# 03_-IMU.net
KiCad netlist of a schematic drawn in Altium Designer
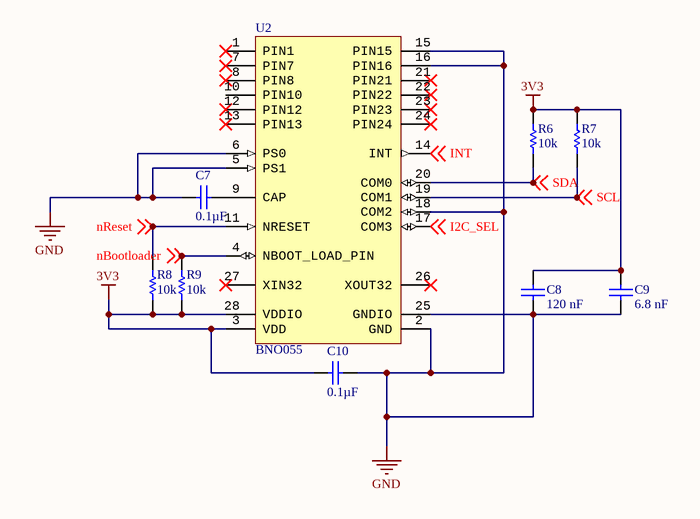
[diagram p0: [03]-IMU.SchDoc]

(export (version "E")
  (design (tool "Eeschema 10.0.6"))
  (components
    (comp (ref "C7")
      (value "C2012X7R2A104K125AA")
      (footprint "CAPC2013X145X20ML20")
      (description "Chip Capacitor, 100 nF, +/- 10%, 100 V, -55 to 1255 degC, 0805 (2012 Metric), RoHS, Tape and Reel")
      (fields
        (field (name "MANUFACTURER") "TDK")
        (field (name "TOLERANCE") "±10%")
        (field (name "CAPACITANCE") "0.1µF")
      )
      (libsource (lib "Altium Content Vault") (part "CAP-NP-2"))
    )
    (comp (ref "C8")
      (value "120 nF")
      (footprint "CAPC1005X55X25ML05T10")
      (description "120 nF Capacitor")
      (fields (field (name "PART NUMBER") "GRM155R71H123KA12D") (field (name "MANUFACTURER") "Murata"))
      (libsource (lib "Altium Content Vault") (part "CAP"))
    )
    (comp (ref "C9")
      (value "6.8 nF")
      (footprint "CAPC0603X33X15NL03T05")
      (fields (field (name "PART NUMBER") "GRM033R71A682KA01D") (field (name "MANUFACTURER") "Murata"))
      (libsource (lib "Altium Content Vault") (part "CAP"))
    )
    (comp (ref "C10")
      (value "C2012X7R2A104K125AA")
      (footprint "CAPC2013X145X20ML20")
      (description "Chip Capacitor, 100 nF, +/- 10%, 100 V, -55 to 1255 degC, 0805 (2012 Metric), RoHS, Tape and Reel")
      (fields
        (field (name "MANUFACTURER") "TDK")
        (field (name "TOLERANCE") "±10%")
        (field (name "CAPACITANCE") "0.1µF")
      )
      (libsource (lib "Altium Content Vault") (part "CAP-NP-2"))
    )
    (comp (ref "R6")
      (value "RC0805JR-0710KL")
      (footprint "RESC2013X60X35ML10T20")
      (description "Chip Resistor, 10 KOhm, +/- 5%, 0.125 W, -55 to 155 degC, 0805 (2012 Metric), RoHS, Tape and Reel")
      (fields (field (name "MANUFACTURER") "Yageo") (field (name "RESISTANCE") "10k"))
      (libsource (lib "Altium Content Vault") (part "RES-2"))
    )
    (comp (ref "R7")
      (value "RC0805JR-0710KL")
      (footprint "RESC2013X60X35ML10T20")
      (description "Chip Resistor, 10 KOhm, +/- 5%, 0.125 W, -55 to 155 degC, 0805 (2012 Metric), RoHS, Tape and Reel")
      (fields (field (name "MANUFACTURER") "Yageo") (field (name "RESISTANCE") "10k"))
      (libsource (lib "Altium Content Vault") (part "RES-2"))
    )
    (comp (ref "R8")
      (value "RC0805JR-0710KL")
      (footprint "RESC2013X60X35ML10T20")
      (description "Chip Resistor, 10 KOhm, +/- 5%, 0.125 W, -55 to 155 degC, 0805 (2012 Metric), RoHS, Tape and Reel")
      (fields (field (name "MANUFACTURER") "Yageo") (field (name "RESISTANCE") "10k"))
      (libsource (lib "Altium Content Vault") (part "RES-2"))
    )
    (comp (ref "R9")
      (value "RC0805JR-0710KL")
      (footprint "RESC2013X60X35ML10T20")
      (description "Chip Resistor, 10 KOhm, +/- 5%, 0.125 W, -55 to 155 degC, 0805 (2012 Metric), RoHS, Tape and Reel")
      (fields (field (name "MANUFACTURER") "Yageo") (field (name "RESISTANCE") "10k"))
      (libsource (lib "Altium Content Vault") (part "RES-2"))
    )
    (comp (ref "U2")
      (value "BNO055")
      (footprint "BOSC-LGA-28_M")
      (fields (field (name "MANUFACTURER") "Bosch Sensortec"))
      (libsource (lib "Altium Content Vault") (part "BOSC-BNO055-LGA-28"))
    )
  )
  (nets
    (net (code "1") (name "3V3") (class "Default")
      (node (ref "C10") (pin "2") (pinfunction "2_2") (pintype "passive"))
      (node (ref "C8") (pin "2") (pinfunction "2_2") (pintype "passive"))
      (node (ref "C9") (pin "2") (pinfunction "2_2") (pintype "passive"))
      (node (ref "R6") (pin "2") (pinfunction "2_2") (pintype "passive"))
      (node (ref "R7") (pin "2") (pinfunction "2_2") (pintype "passive"))
      (node (ref "R8") (pin "1") (pinfunction "1_1") (pintype "passive"))
      (node (ref "R9") (pin "1") (pinfunction "1_1") (pintype "passive"))
      (node (ref "U2") (pin "28") (pinfunction "VDDIO_28") (pintype "power_in"))
      (node (ref "U2") (pin "3") (pinfunction "VDD_3") (pintype "power_in"))
    )
    (net (code "2") (name "GND") (class "Default")
      (node (ref "C10") (pin "1") (pinfunction "1_1") (pintype "passive"))
      (node (ref "C7") (pin "2") (pinfunction "2_2") (pintype "passive"))
      (node (ref "C8") (pin "1") (pinfunction "1_1") (pintype "passive"))
      (node (ref "C9") (pin "1") (pinfunction "1_1") (pintype "passive"))
      (node (ref "U2") (pin "15") (pinfunction "PIN15_15") (pintype "power_in"))
      (node (ref "U2") (pin "16") (pinfunction "PIN16_16") (pintype "power_in"))
      (node (ref "U2") (pin "18") (pinfunction "COM2_18") (pintype "bidirectional"))
      (node (ref "U2") (pin "2") (pinfunction "GND_2") (pintype "power_in"))
      (node (ref "U2") (pin "25") (pinfunction "GNDIO_25") (pintype "power_in"))
      (node (ref "U2") (pin "5") (pinfunction "PS1_5") (pintype "input"))
      (node (ref "U2") (pin "6") (pinfunction "PS0_6") (pintype "input"))
    )
    (net (code "3") (name "I2C_SEL") (class "Default")
      (node (ref "U2") (pin "17") (pinfunction "COM3_17") (pintype "bidirectional"))
    )
    (net (code "4") (name "INT") (class "Default")
      (node (ref "U2") (pin "14") (pinfunction "INT_14") (pintype "output"))
    )
    (net (code "5") (name "Net-(U2-CAP)") (class "Default")
      (node (ref "C7") (pin "1") (pinfunction "1_1") (pintype "passive"))
      (node (ref "U2") (pin "9") (pinfunction "CAP_9") (pintype "passive"))
    )
    (net (code "6") (name "SCL") (class "Default")
      (node (ref "R7") (pin "1") (pinfunction "1_1") (pintype "passive"))
      (node (ref "U2") (pin "19") (pinfunction "COM1_19") (pintype "bidirectional"))
    )
    (net (code "7") (name "SDA") (class "Default")
      (node (ref "R6") (pin "1") (pinfunction "1_1") (pintype "passive"))
      (node (ref "U2") (pin "20") (pinfunction "COM0_20") (pintype "bidirectional"))
    )
    (net (code "8") (name "nBootloader") (class "Default")
      (node (ref "R9") (pin "2") (pinfunction "2_2") (pintype "passive"))
      (node (ref "U2") (pin "4") (pinfunction "NBOOT_LOAD_PIN_4") (pintype "bidirectional"))
    )
    (net (code "9") (name "nReset") (class "Default")
      (node (ref "R8") (pin "2") (pinfunction "2_2") (pintype "passive"))
      (node (ref "U2") (pin "11") (pinfunction "NRESET_11") (pintype "input"))
    )
    (net (code "10") (name "unconnected-(U2-PIN1-Pad1)") (class "Default")
      (node (ref "U2") (pin "1") (pinfunction "PIN1_1") (pintype "passive+no_connect"))
    )
    (net (code "11") (name "unconnected-(U2-PIN7-Pad7)") (class "Default")
      (node (ref "U2") (pin "7") (pinfunction "PIN7_7") (pintype "passive+no_connect"))
    )
    (net (code "12") (name "unconnected-(U2-PIN8-Pad8)") (class "Default")
      (node (ref "U2") (pin "8") (pinfunction "PIN8_8") (pintype "passive+no_connect"))
    )
    (net (code "13") (name "unconnected-(U2-PIN10-Pad10)") (class "Default")
      (node (ref "U2") (pin "10") (pinfunction "PIN10_10") (pintype "power_in"))
    )
    (net (code "14") (name "unconnected-(U2-PIN12-Pad12)") (class "Default")
      (node (ref "U2") (pin "12") (pinfunction "PIN12_12") (pintype "passive+no_connect"))
    )
    (net (code "15") (name "unconnected-(U2-PIN13-Pad13)") (class "Default")
      (node (ref "U2") (pin "13") (pinfunction "PIN13_13") (pintype "passive+no_connect"))
    )
    (net (code "16") (name "unconnected-(U2-PIN21-Pad21)") (class "Default")
      (node (ref "U2") (pin "21") (pinfunction "PIN21_21") (pintype "passive+no_connect"))
    )
    (net (code "17") (name "unconnected-(U2-PIN22-Pad22)") (class "Default")
      (node (ref "U2") (pin "22") (pinfunction "PIN22_22") (pintype "passive+no_connect"))
    )
    (net (code "18") (name "unconnected-(U2-PIN23-Pad23)") (class "Default")
      (node (ref "U2") (pin "23") (pinfunction "PIN23_23") (pintype "passive+no_connect"))
    )
    (net (code "19") (name "unconnected-(U2-PIN24-Pad24)") (class "Default")
      (node (ref "U2") (pin "24") (pinfunction "PIN24_24") (pintype "passive+no_connect"))
    )
    (net (code "20") (name "unconnected-(U2-XIN32-Pad27)") (class "Default")
      (node (ref "U2") (pin "27") (pinfunction "XIN32_27") (pintype "passive+no_connect"))
    )
    (net (code "21") (name "unconnected-(U2-XOUT32-Pad26)") (class "Default")
      (node (ref "U2") (pin "26") (pinfunction "XOUT32_26") (pintype "passive+no_connect"))
    )
  )
)
